# P1_Final.net
KiCad netlist of a schematic drawn in Altium Designer
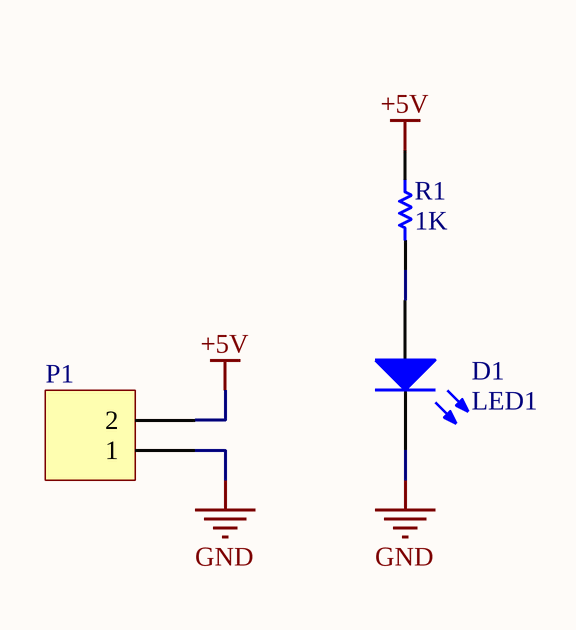
[diagram p0: P1_Final.SchDoc]

(export (version "E")
  (design (tool "Eeschema 10.0.6"))
  (components
    (comp (ref "D1")
      (value "LED1")
      (footprint "LED-1")
      (description "Typical RED GaAs LED")
      (fields (field (name "PUBLISHER") "Altium Limited"))
      (libsource (lib "Miscellaneous Devices") (part "LED1"))
    )
    (comp (ref "P1")
      (value "Header 2")
      (footprint "HDR1X2")
      (description "Header, 2-Pin")
      (fields (field (name "PUBLISHER") "Altium Limited"))
      (libsource (lib "Miscellaneous Connectors") (part "Header 2"))
    )
    (comp (ref "R1")
      (value "1K")
      (footprint "AXIAL-0.3")
      (description "Resistor")
      (fields (field (name "Comment") "Res1") (field (name "PUBLISHER") "Altium Limited"))
      (libsource (lib "Miscellaneous Devices") (part "Res1"))
    )
  )
  (nets
    (net (code "1") (name "+5V") (class "Default")
      (node (ref "P1") (pin "2") (pinfunction "2_2") (pintype "passive"))
      (node (ref "R1") (pin "1") (pinfunction "1_1") (pintype "passive"))
    )
    (net (code "2") (name "GND") (class "Default")
      (node (ref "D1") (pin "2") (pinfunction "K_2") (pintype "passive"))
      (node (ref "P1") (pin "1") (pinfunction "1_1") (pintype "passive"))
    )
    (net (code "3") (name "Net-(D1-A)") (class "Default")
      (node (ref "D1") (pin "1") (pinfunction "A_1") (pintype "passive"))
      (node (ref "R1") (pin "2") (pinfunction "2_2") (pintype "passive"))
    )
  )
)
